# mwscoretransponder2017.net
KiCad netlist of a schematic drawn in EAGLE
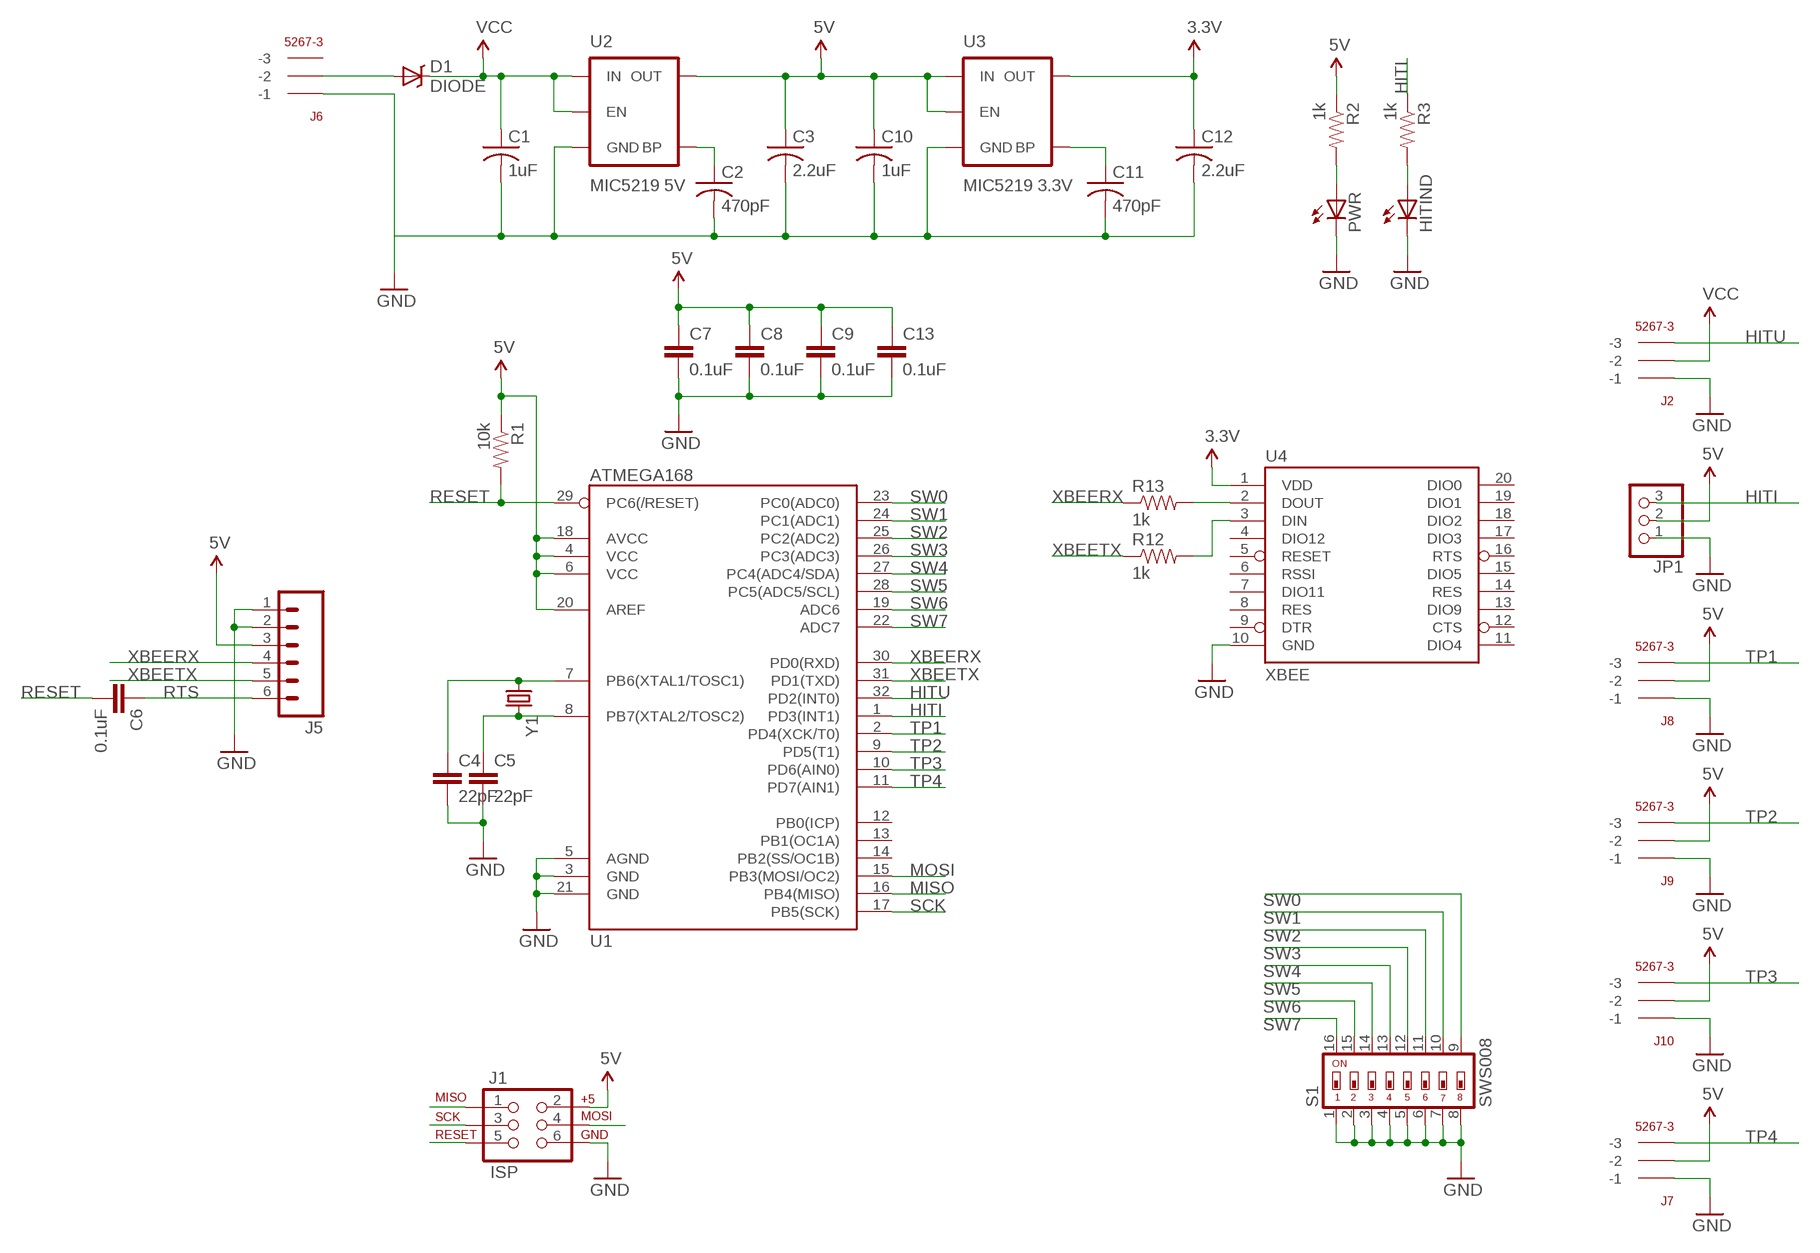
[diagram p0: schematic, sheet 1]

(export (version "E")
  (design (tool "Eeschema 10.0.6"))
  (components
    (comp (ref "C1")
      (value "1uF")
      (footprint "eagle-import:C0603")
      (libsource (lib "eagle-import") (part "C-USC0603"))
    )
    (comp (ref "C2")
      (value "470pF")
      (footprint "eagle-import:C0603")
      (libsource (lib "eagle-import") (part "C-USC0603"))
    )
    (comp (ref "C3")
      (value "2.2uF")
      (footprint "eagle-import:C0805")
      (libsource (lib "eagle-import") (part "C-USC0805"))
    )
    (comp (ref "C4")
      (value "22pF")
      (footprint "eagle-import:0603-CAP")
      (libsource (lib "eagle-import") (part "CAP0603-CAP"))
    )
    (comp (ref "C5")
      (value "22pF")
      (footprint "eagle-import:0603-CAP")
      (libsource (lib "eagle-import") (part "CAP0603-CAP"))
    )
    (comp (ref "C6")
      (value "0.1uF")
      (footprint "eagle-import:0603-CAP")
      (libsource (lib "eagle-import") (part "CAP0603-CAP"))
    )
    (comp (ref "C7")
      (value "0.1uF")
      (footprint "eagle-import:0603-CAP")
      (libsource (lib "eagle-import") (part "CAP0603-CAP"))
    )
    (comp (ref "C8")
      (value "0.1uF")
      (footprint "eagle-import:0603-CAP")
      (libsource (lib "eagle-import") (part "CAP0603-CAP"))
    )
    (comp (ref "C9")
      (value "0.1uF")
      (footprint "eagle-import:0603-CAP")
      (libsource (lib "eagle-import") (part "CAP0603-CAP"))
    )
    (comp (ref "C10")
      (value "1uF")
      (footprint "eagle-import:C0603")
      (libsource (lib "eagle-import") (part "C-USC0603"))
    )
    (comp (ref "C11")
      (value "470pF")
      (footprint "eagle-import:C0603")
      (libsource (lib "eagle-import") (part "C-USC0603"))
    )
    (comp (ref "C12")
      (value "2.2uF")
      (footprint "eagle-import:C0805")
      (libsource (lib "eagle-import") (part "C-USC0805"))
    )
    (comp (ref "C13")
      (value "0.1uF")
      (footprint "eagle-import:0603-CAP")
      (libsource (lib "eagle-import") (part "CAP0603-CAP"))
    )
    (comp (ref "D1")
      (value "DIODE")
      (footprint "eagle-import:SMA-DIODE")
      (libsource (lib "eagle-import") (part "DIODE-SCHOTTKY_"))
    )
    (comp (ref "HITIND")
      (value "LED0603")
      (footprint "eagle-import:LED-0603")
      (libsource (lib "eagle-import") (part "LED0603"))
    )
    (comp (ref "J1")
      (value "ISP")
      (footprint "eagle-import:2X3")
      (libsource (lib "eagle-import") (part "AVR_SPI_PRG_6PTH"))
    )
    (comp (ref "J2")
      (value "5267-3")
      (footprint "eagle-import:5267-3")
      (libsource (lib "eagle-import") (part "5267-3"))
    )
    (comp (ref "J5")
      (value "M06SIP")
      (footprint "eagle-import:1X06")
      (libsource (lib "eagle-import") (part "M06SIP"))
    )
    (comp (ref "J6")
      (value "5267-3")
      (footprint "eagle-import:5267-3")
      (libsource (lib "eagle-import") (part "5267-3"))
    )
    (comp (ref "J7")
      (value "5267-3")
      (footprint "eagle-import:5267-3")
      (libsource (lib "eagle-import") (part "5267-3"))
    )
    (comp (ref "J8")
      (value "5267-3")
      (footprint "eagle-import:5267-3")
      (libsource (lib "eagle-import") (part "5267-3"))
    )
    (comp (ref "J9")
      (value "5267-3")
      (footprint "eagle-import:5267-3")
      (libsource (lib "eagle-import") (part "5267-3"))
    )
    (comp (ref "J10")
      (value "5267-3")
      (footprint "eagle-import:5267-3")
      (libsource (lib "eagle-import") (part "5267-3"))
    )
    (comp (ref "JP1")
      (value "PINHD-1X3")
      (footprint "eagle-import:1X03")
      (libsource (lib "eagle-import") (part "PINHD-1X3"))
    )
    (comp (ref "PWR")
      (value "LED0603")
      (footprint "eagle-import:LED-0603")
      (libsource (lib "eagle-import") (part "LED0603"))
    )
    (comp (ref "R1")
      (value "10k")
      (footprint "eagle-import:0603-RES")
      (libsource (lib "eagle-import") (part "RESISTOR0603-RES"))
    )
    (comp (ref "R2")
      (value "1k")
      (footprint "eagle-import:0603-RES")
      (libsource (lib "eagle-import") (part "RESISTOR0603-RES"))
    )
    (comp (ref "R3")
      (value "1k")
      (footprint "eagle-import:0603-RES")
      (libsource (lib "eagle-import") (part "RESISTOR0603-RES"))
    )
    (comp (ref "R12")
      (value "1k")
      (footprint "eagle-import:0603-RES")
      (libsource (lib "eagle-import") (part "RESISTOR0603-RES"))
    )
    (comp (ref "R13")
      (value "1k")
      (footprint "eagle-import:0603-RES")
      (libsource (lib "eagle-import") (part "RESISTOR0603-RES"))
    )
    (comp (ref "S1")
      (value "SWS008")
      (footprint "eagle-import:SMS-008")
      (libsource (lib "eagle-import") (part "SWS008"))
    )
    (comp (ref "U1")
      (value "ATMEGA168")
      (footprint "eagle-import:TQFP32-08")
      (libsource (lib "eagle-import") (part "ATMEGA168"))
    )
    (comp (ref "U2")
      (value "MIC5219 5V")
      (footprint "eagle-import:SOT23-5")
      (libsource (lib "eagle-import") (part "V_REG_MIC52195V"))
    )
    (comp (ref "U3")
      (value "MIC5219 3.3V")
      (footprint "eagle-import:SOT23-5")
      (libsource (lib "eagle-import") (part "V_REG_MIC52193.3V"))
    )
    (comp (ref "U4")
      (value "XBEE")
      (footprint "eagle-import:XBEE-SMD")
      (libsource (lib "eagle-import") (part "XBEE-1B3"))
    )
    (comp (ref "Y1")
      (value "CRYSTAL5X3")
      (footprint "eagle-import:CRYSTAL-SMD-5X3")
      (libsource (lib "eagle-import") (part "CRYSTAL5X3"))
    )
  )
  (nets
    (net (code "1") (name "/HITI") (class "Default")
      (node (ref "JP1") (pin "3") (pinfunction "3_3") (pintype "passive"))
      (node (ref "R3") (pin "1") (pinfunction "1_1") (pintype "passive"))
      (node (ref "U1") (pin "1") (pinfunction "PD3(INT1)_1") (pintype "bidirectional"))
    )
    (net (code "2") (name "/HITU") (class "Default")
      (node (ref "J2") (pin "P$3") (pinfunction "-3_P$3") (pintype "bidirectional"))
      (node (ref "U1") (pin "32") (pinfunction "PD2(INT0)_32") (pintype "bidirectional"))
    )
    (net (code "3") (name "/MISO") (class "Default")
      (node (ref "J1") (pin "1") (pinfunction "1_1") (pintype "passive"))
      (node (ref "U1") (pin "16") (pinfunction "PB4(MISO)_16") (pintype "bidirectional"))
    )
    (net (code "4") (name "/MOSI") (class "Default")
      (node (ref "J1") (pin "4") (pinfunction "4_4") (pintype "passive"))
      (node (ref "U1") (pin "15") (pinfunction "PB3(MOSI/OC2)_15") (pintype "bidirectional"))
    )
    (net (code "5") (name "/RESET") (class "Default")
      (node (ref "C6") (pin "2") (pinfunction "2_2") (pintype "passive"))
      (node (ref "J1") (pin "5") (pinfunction "5_5") (pintype "passive"))
      (node (ref "R1") (pin "2") (pinfunction "2_2") (pintype "passive"))
      (node (ref "U1") (pin "29") (pinfunction "PC6(/RESET)_29") (pintype "bidirectional"))
    )
    (net (code "6") (name "/RTS") (class "Default")
      (node (ref "C6") (pin "1") (pinfunction "1_1") (pintype "passive"))
      (node (ref "J5") (pin "6") (pinfunction "6_6") (pintype "passive"))
    )
    (net (code "7") (name "/SCK") (class "Default")
      (node (ref "J1") (pin "3") (pinfunction "3_3") (pintype "passive"))
      (node (ref "U1") (pin "17") (pinfunction "PB5(SCK)_17") (pintype "bidirectional"))
    )
    (net (code "8") (name "/SW0") (class "Default")
      (node (ref "S1") (pin "9") (pinfunction "9_9") (pintype "passive"))
      (node (ref "U1") (pin "23") (pinfunction "PC0(ADC0)_23") (pintype "bidirectional"))
    )
    (net (code "9") (name "/SW1") (class "Default")
      (node (ref "S1") (pin "10") (pinfunction "10_10") (pintype "passive"))
      (node (ref "U1") (pin "24") (pinfunction "PC1(ADC1)_24") (pintype "bidirectional"))
    )
    (net (code "10") (name "/SW2") (class "Default")
      (node (ref "S1") (pin "11") (pinfunction "11_11") (pintype "passive"))
      (node (ref "U1") (pin "25") (pinfunction "PC2(ADC2)_25") (pintype "bidirectional"))
    )
    (net (code "11") (name "/SW3") (class "Default")
      (node (ref "S1") (pin "12") (pinfunction "12_12") (pintype "passive"))
      (node (ref "U1") (pin "26") (pinfunction "PC3(ADC3)_26") (pintype "bidirectional"))
    )
    (net (code "12") (name "/SW4") (class "Default")
      (node (ref "S1") (pin "13") (pinfunction "13_13") (pintype "passive"))
      (node (ref "U1") (pin "27") (pinfunction "PC4(ADC4/SDA)_27") (pintype "bidirectional"))
    )
    (net (code "13") (name "/SW5") (class "Default")
      (node (ref "S1") (pin "14") (pinfunction "14_14") (pintype "passive"))
      (node (ref "U1") (pin "28") (pinfunction "PC5(ADC5/SCL)_28") (pintype "bidirectional"))
    )
    (net (code "14") (name "/SW6") (class "Default")
      (node (ref "S1") (pin "15") (pinfunction "15_15") (pintype "passive"))
      (node (ref "U1") (pin "19") (pinfunction "ADC6_19") (pintype "bidirectional"))
    )
    (net (code "15") (name "/SW7") (class "Default")
      (node (ref "S1") (pin "16") (pinfunction "16_16") (pintype "passive"))
      (node (ref "U1") (pin "22") (pinfunction "ADC7_22") (pintype "bidirectional"))
    )
    (net (code "16") (name "/TP1") (class "Default")
      (node (ref "J8") (pin "P$3") (pinfunction "-3_P$3") (pintype "bidirectional"))
      (node (ref "U1") (pin "2") (pinfunction "PD4(XCK/T0)_2") (pintype "bidirectional"))
    )
    (net (code "17") (name "/TP2") (class "Default")
      (node (ref "J9") (pin "P$3") (pinfunction "-3_P$3") (pintype "bidirectional"))
      (node (ref "U1") (pin "9") (pinfunction "PD5(T1)_9") (pintype "bidirectional"))
    )
    (net (code "18") (name "/TP3") (class "Default")
      (node (ref "J10") (pin "P$3") (pinfunction "-3_P$3") (pintype "bidirectional"))
      (node (ref "U1") (pin "10") (pinfunction "PD6(AIN0)_10") (pintype "bidirectional"))
    )
    (net (code "19") (name "/TP4") (class "Default")
      (node (ref "J7") (pin "P$3") (pinfunction "-3_P$3") (pintype "bidirectional"))
      (node (ref "U1") (pin "11") (pinfunction "PD7(AIN1)_11") (pintype "bidirectional"))
    )
    (net (code "20") (name "/XBEERX") (class "Default")
      (node (ref "J5") (pin "4") (pinfunction "4_4") (pintype "passive"))
      (node (ref "R13") (pin "1") (pinfunction "1_1") (pintype "passive"))
      (node (ref "U1") (pin "30") (pinfunction "PD0(RXD)_30") (pintype "bidirectional"))
    )
    (net (code "21") (name "/XBEETX") (class "Default")
      (node (ref "J5") (pin "5") (pinfunction "5_5") (pintype "passive"))
      (node (ref "R12") (pin "1") (pinfunction "1_1") (pintype "passive"))
      (node (ref "U1") (pin "31") (pinfunction "PD1(TXD)_31") (pintype "bidirectional"))
    )
    (net (code "22") (name "3.3V") (class "Default")
      (node (ref "C12") (pin "1") (pinfunction "1_1") (pintype "passive"))
      (node (ref "U3") (pin "5") (pinfunction "OUT_5") (pintype "passive"))
      (node (ref "U4") (pin "1") (pinfunction "VDD_1") (pintype "power_in"))
    )
    (net (code "23") (name "5V") (class "Default")
      (node (ref "C10") (pin "1") (pinfunction "1_1") (pintype "passive"))
      (node (ref "C13") (pin "1") (pinfunction "1_1") (pintype "passive"))
      (node (ref "C3") (pin "1") (pinfunction "1_1") (pintype "passive"))
      (node (ref "C7") (pin "1") (pinfunction "1_1") (pintype "passive"))
      (node (ref "C8") (pin "1") (pinfunction "1_1") (pintype "passive"))
      (node (ref "C9") (pin "1") (pinfunction "1_1") (pintype "passive"))
      (node (ref "J1") (pin "2") (pinfunction "2_2") (pintype "passive"))
      (node (ref "J10") (pin "P$2") (pinfunction "-2_P$2") (pintype "bidirectional"))
      (node (ref "J5") (pin "3") (pinfunction "3_3") (pintype "passive"))
      (node (ref "J7") (pin "P$2") (pinfunction "-2_P$2") (pintype "bidirectional"))
      (node (ref "J8") (pin "P$2") (pinfunction "-2_P$2") (pintype "bidirectional"))
      (node (ref "J9") (pin "P$2") (pinfunction "-2_P$2") (pintype "bidirectional"))
      (node (ref "JP1") (pin "2") (pinfunction "2_2") (pintype "passive"))
      (node (ref "R1") (pin "1") (pinfunction "1_1") (pintype "passive"))
      (node (ref "R2") (pin "1") (pinfunction "1_1") (pintype "passive"))
      (node (ref "U1") (pin "18") (pinfunction "AVCC_18") (pintype "bidirectional"))
      (node (ref "U1") (pin "20") (pinfunction "AREF_20") (pintype "bidirectional"))
      (node (ref "U1") (pin "4") (pinfunction "VCC_4") (pintype "bidirectional"))
      (node (ref "U1") (pin "6") (pinfunction "VCC_6") (pintype "bidirectional"))
      (node (ref "U2") (pin "5") (pinfunction "OUT_5") (pintype "passive"))
      (node (ref "U3") (pin "1") (pinfunction "IN_1") (pintype "input"))
      (node (ref "U3") (pin "3") (pinfunction "EN_3") (pintype "input"))
    )
    (net (code "24") (name "GND") (class "Default")
      (node (ref "C1") (pin "2") (pinfunction "2_2") (pintype "passive"))
      (node (ref "C10") (pin "2") (pinfunction "2_2") (pintype "passive"))
      (node (ref "C11") (pin "2") (pinfunction "2_2") (pintype "passive"))
      (node (ref "C12") (pin "2") (pinfunction "2_2") (pintype "passive"))
      (node (ref "C13") (pin "2") (pinfunction "2_2") (pintype "passive"))
      (node (ref "C2") (pin "2") (pinfunction "2_2") (pintype "passive"))
      (node (ref "C3") (pin "2") (pinfunction "2_2") (pintype "passive"))
      (node (ref "C4") (pin "2") (pinfunction "2_2") (pintype "passive"))
      (node (ref "C5") (pin "2") (pinfunction "2_2") (pintype "passive"))
      (node (ref "C7") (pin "2") (pinfunction "2_2") (pintype "passive"))
      (node (ref "C8") (pin "2") (pinfunction "2_2") (pintype "passive"))
      (node (ref "C9") (pin "2") (pinfunction "2_2") (pintype "passive"))
      (node (ref "HITIND") (pin "C") (pinfunction "C_C") (pintype "passive"))
      (node (ref "J1") (pin "6") (pinfunction "6_6") (pintype "passive"))
      (node (ref "J10") (pin "P$1") (pinfunction "-1_P$1") (pintype "bidirectional"))
      (node (ref "J2") (pin "P$1") (pinfunction "-1_P$1") (pintype "bidirectional"))
      (node (ref "J5") (pin "1") (pinfunction "1_1") (pintype "passive"))
      (node (ref "J5") (pin "2") (pinfunction "2_2") (pintype "passive"))
      (node (ref "J6") (pin "P$1") (pinfunction "-1_P$1") (pintype "bidirectional"))
      (node (ref "J7") (pin "P$1") (pinfunction "-1_P$1") (pintype "bidirectional"))
      (node (ref "J8") (pin "P$1") (pinfunction "-1_P$1") (pintype "bidirectional"))
      (node (ref "J9") (pin "P$1") (pinfunction "-1_P$1") (pintype "bidirectional"))
      (node (ref "JP1") (pin "1") (pinfunction "1_1") (pintype "passive"))
      (node (ref "PWR") (pin "C") (pinfunction "C_C") (pintype "passive"))
      (node (ref "S1") (pin "1") (pinfunction "1_1") (pintype "passive"))
      (node (ref "S1") (pin "2") (pinfunction "2_2") (pintype "passive"))
      (node (ref "S1") (pin "3") (pinfunction "3_3") (pintype "passive"))
      (node (ref "S1") (pin "4") (pinfunction "4_4") (pintype "passive"))
      (node (ref "S1") (pin "5") (pinfunction "5_5") (pintype "passive"))
      (node (ref "S1") (pin "6") (pinfunction "6_6") (pintype "passive"))
      (node (ref "S1") (pin "7") (pinfunction "7_7") (pintype "passive"))
      (node (ref "S1") (pin "8") (pinfunction "8_8") (pintype "passive"))
      (node (ref "U1") (pin "21") (pinfunction "GND_21") (pintype "bidirectional"))
      (node (ref "U1") (pin "3") (pinfunction "GND_3") (pintype "bidirectional"))
      (node (ref "U1") (pin "5") (pinfunction "AGND_5") (pintype "bidirectional"))
      (node (ref "U2") (pin "2") (pinfunction "GND_2") (pintype "input"))
      (node (ref "U3") (pin "2") (pinfunction "GND_2") (pintype "input"))
      (node (ref "U4") (pin "10") (pinfunction "GND_10") (pintype "power_in"))
    )
    (net (code "25") (name "Net-(HITIND-PadA)") (class "Default")
      (node (ref "HITIND") (pin "A") (pinfunction "A_A") (pintype "passive"))
      (node (ref "R3") (pin "2") (pinfunction "2_2") (pintype "passive"))
    )
    (net (code "26") (name "Net-(J6--2)") (class "Default")
      (node (ref "D1") (pin "A") (pinfunction "A_A") (pintype "passive"))
      (node (ref "J6") (pin "P$2") (pinfunction "-2_P$2") (pintype "bidirectional"))
    )
    (net (code "27") (name "Net-(PWR-PadA)") (class "Default")
      (node (ref "PWR") (pin "A") (pinfunction "A_A") (pintype "passive"))
      (node (ref "R2") (pin "2") (pinfunction "2_2") (pintype "passive"))
    )
    (net (code "28") (name "Net-(U1-PB6(XTAL1{slash}TOSC1))") (class "Default")
      (node (ref "C4") (pin "1") (pinfunction "1_1") (pintype "passive"))
      (node (ref "U1") (pin "7") (pinfunction "PB6(XTAL1/TOSC1)_7") (pintype "bidirectional"))
      (node (ref "Y1") (pin "1") (pinfunction "1_1") (pintype "passive"))
    )
    (net (code "29") (name "Net-(U1-PB7(XTAL2{slash}TOSC2))") (class "Default")
      (node (ref "C5") (pin "1") (pinfunction "1_1") (pintype "passive"))
      (node (ref "U1") (pin "8") (pinfunction "PB7(XTAL2/TOSC2)_8") (pintype "bidirectional"))
      (node (ref "Y1") (pin "3") (pinfunction "2_3") (pintype "passive"))
    )
    (net (code "30") (name "Net-(U2-BP)") (class "Default")
      (node (ref "C2") (pin "1") (pinfunction "1_1") (pintype "passive"))
      (node (ref "U2") (pin "4") (pinfunction "BP_4") (pintype "input"))
    )
    (net (code "31") (name "Net-(U3-BP)") (class "Default")
      (node (ref "C11") (pin "1") (pinfunction "1_1") (pintype "passive"))
      (node (ref "U3") (pin "4") (pinfunction "BP_4") (pintype "input"))
    )
    (net (code "32") (name "Net-(U4-DIN)") (class "Default")
      (node (ref "R12") (pin "2") (pinfunction "2_2") (pintype "passive"))
      (node (ref "U4") (pin "3") (pinfunction "DIN_3") (pintype "input"))
    )
    (net (code "33") (name "Net-(U4-DOUT)") (class "Default")
      (node (ref "R13") (pin "2") (pinfunction "2_2") (pintype "passive"))
      (node (ref "U4") (pin "2") (pinfunction "DOUT_2") (pintype "output"))
    )
    (net (code "34") (name "VCC") (class "Default")
      (node (ref "C1") (pin "1") (pinfunction "1_1") (pintype "passive"))
      (node (ref "D1") (pin "C") (pinfunction "C_C") (pintype "passive"))
      (node (ref "J2") (pin "P$2") (pinfunction "-2_P$2") (pintype "bidirectional"))
      (node (ref "U2") (pin "1") (pinfunction "IN_1") (pintype "input"))
      (node (ref "U2") (pin "3") (pinfunction "EN_3") (pintype "input"))
    )
    (net (code "35") (name "unconnected-(J6--3-PadP$3)") (class "Default")
      (node (ref "J6") (pin "P$3") (pinfunction "-3_P$3") (pintype "bidirectional"))
    )
    (net (code "36") (name "unconnected-(U1-PB0(ICP)-Pad12)") (class "Default")
      (node (ref "U1") (pin "12") (pinfunction "PB0(ICP)_12") (pintype "bidirectional"))
    )
    (net (code "37") (name "unconnected-(U1-PB1(OC1A)-Pad13)") (class "Default")
      (node (ref "U1") (pin "13") (pinfunction "PB1(OC1A)_13") (pintype "bidirectional"))
    )
    (net (code "38") (name "unconnected-(U1-PB2(SS{slash}OC1B)-Pad14)") (class "Default")
      (node (ref "U1") (pin "14") (pinfunction "PB2(SS/OC1B)_14") (pintype "bidirectional"))
    )
    (net (code "39") (name "unconnected-(U4-CTS-Pad12)") (class "Default")
      (node (ref "U4") (pin "12") (pinfunction "CTS_12") (pintype "output"))
    )
    (net (code "40") (name "unconnected-(U4-DIO0-Pad20)") (class "Default")
      (node (ref "U4") (pin "20") (pinfunction "DIO0_20") (pintype "bidirectional"))
    )
    (net (code "41") (name "unconnected-(U4-DIO1-Pad19)") (class "Default")
      (node (ref "U4") (pin "19") (pinfunction "DIO1_19") (pintype "bidirectional"))
    )
    (net (code "42") (name "unconnected-(U4-DIO2-Pad18)") (class "Default")
      (node (ref "U4") (pin "18") (pinfunction "DIO2_18") (pintype "bidirectional"))
    )
    (net (code "43") (name "unconnected-(U4-DIO3-Pad17)") (class "Default")
      (node (ref "U4") (pin "17") (pinfunction "DIO3_17") (pintype "bidirectional"))
    )
    (net (code "44") (name "unconnected-(U4-DIO4-Pad11)") (class "Default")
      (node (ref "U4") (pin "11") (pinfunction "DIO4_11") (pintype "bidirectional"))
    )
    (net (code "45") (name "unconnected-(U4-DIO5-Pad15)") (class "Default")
      (node (ref "U4") (pin "15") (pinfunction "DIO5_15") (pintype "bidirectional"))
    )
    (net (code "46") (name "unconnected-(U4-DIO9-Pad13)") (class "Default")
      (node (ref "U4") (pin "13") (pinfunction "DIO9_13") (pintype "bidirectional"))
    )
    (net (code "47") (name "unconnected-(U4-DIO11-Pad7)") (class "Default")
      (node (ref "U4") (pin "7") (pinfunction "DIO11_7") (pintype "bidirectional"))
    )
    (net (code "48") (name "unconnected-(U4-DIO12-Pad4)") (class "Default")
      (node (ref "U4") (pin "4") (pinfunction "DIO12_4") (pintype "bidirectional"))
    )
    (net (code "49") (name "unconnected-(U4-DTR-Pad9)") (class "Default")
      (node (ref "U4") (pin "9") (pinfunction "DTR_9") (pintype "bidirectional"))
    )
    (net (code "50") (name "unconnected-(U4-RES-Pad8)") (class "Default")
      (node (ref "U4") (pin "8") (pinfunction "RES_8") (pintype "bidirectional"))
    )
    (net (code "51") (name "unconnected-(U4-RES-Pad14)") (class "Default")
      (node (ref "U4") (pin "14") (pinfunction "RES_14") (pintype "bidirectional"))
    )
    (net (code "52") (name "unconnected-(U4-RESET-Pad5)") (class "Default")
      (node (ref "U4") (pin "5") (pinfunction "RESET_5") (pintype "input"))
    )
    (net (code "53") (name "unconnected-(U4-RSSI-Pad6)") (class "Default")
      (node (ref "U4") (pin "6") (pinfunction "RSSI_6") (pintype "bidirectional"))
    )
    (net (code "54") (name "unconnected-(U4-RTS-Pad16)") (class "Default")
      (node (ref "U4") (pin "16") (pinfunction "RTS_16") (pintype "input"))
    )
  )
)
